# LEDs.net
KiCad netlist of a schematic drawn in Altium Designer
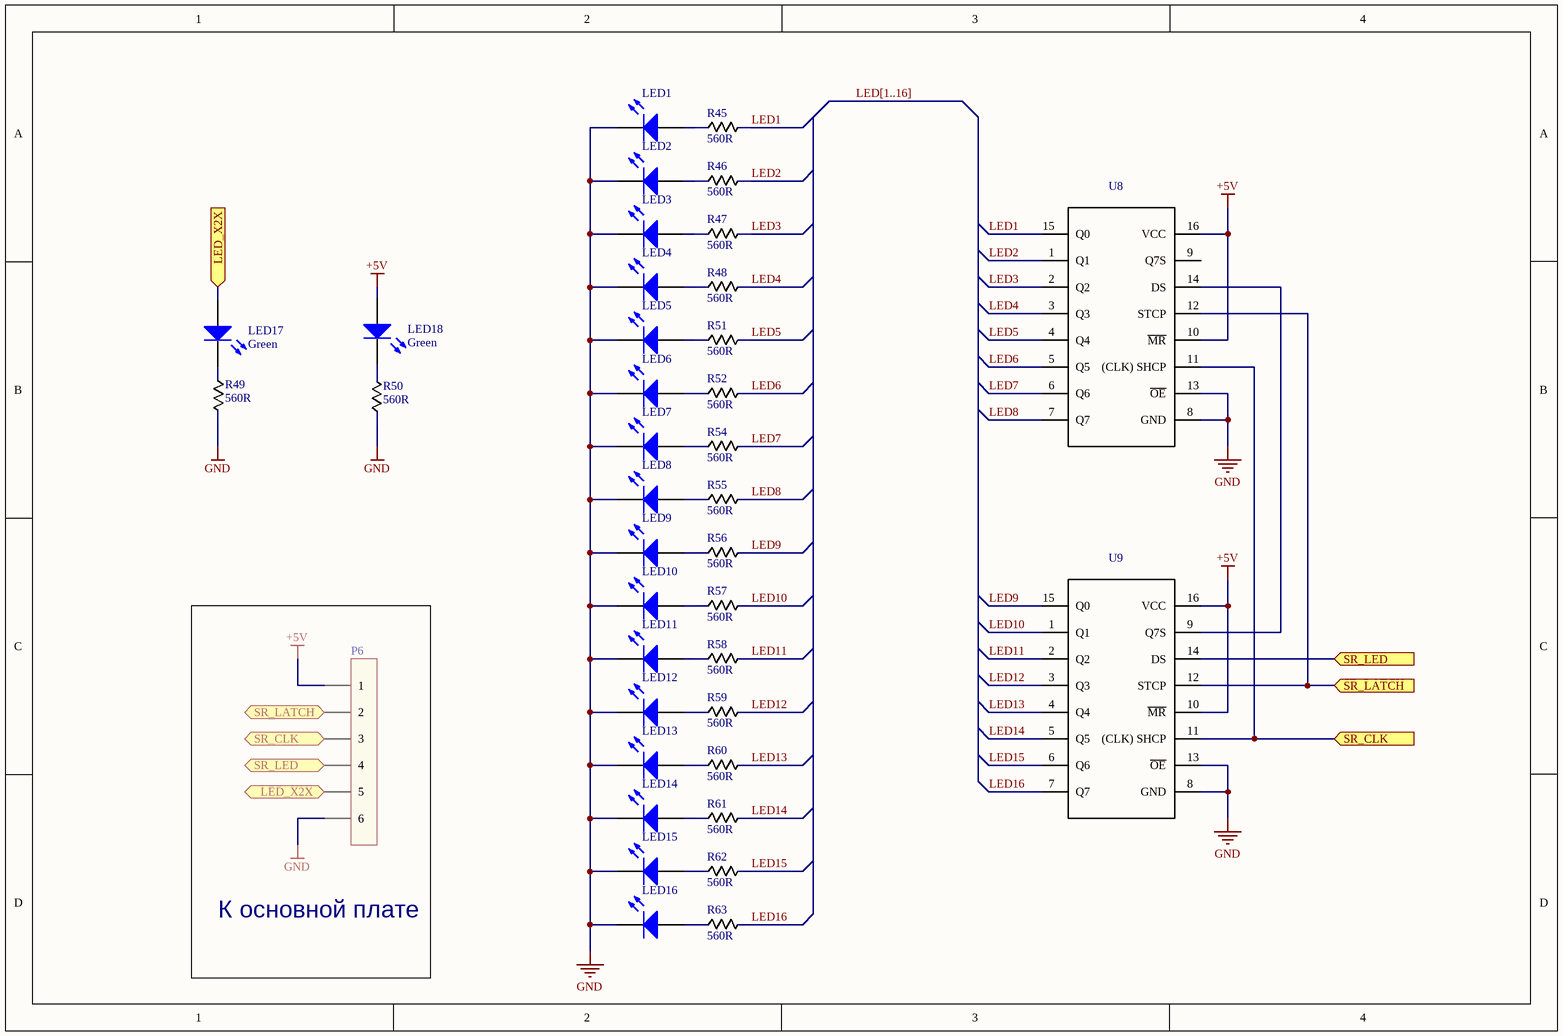
[diagram p0: LEDs.SchDoc]

(export (version "E")
  (design (tool "Eeschema 10.0.6"))
  (components
    (comp (ref "LED1")
      (value "Green")
      (footprint "LED SMD 0603")
      (fields (field (name "PART NUMBER") "KP-1608SGC"))
      (libsource (lib "kontr") (part "0603 LED"))
    )
    (comp (ref "LED2")
      (value "Green")
      (footprint "LED SMD 0603")
      (fields (field (name "PART NUMBER") "KP-1608SGC"))
      (libsource (lib "kontr") (part "0603 LED"))
    )
    (comp (ref "LED3")
      (value "Green")
      (footprint "LED SMD 0603")
      (fields (field (name "PART NUMBER") "KP-1608SGC"))
      (libsource (lib "kontr") (part "0603 LED"))
    )
    (comp (ref "LED4")
      (value "Green")
      (footprint "LED SMD 0603")
      (fields (field (name "PART NUMBER") "KP-1608SGC"))
      (libsource (lib "kontr") (part "0603 LED"))
    )
    (comp (ref "LED5")
      (value "Green")
      (footprint "LED SMD 0603")
      (fields (field (name "PART NUMBER") "KP-1608SGC"))
      (libsource (lib "kontr") (part "0603 LED"))
    )
    (comp (ref "LED6")
      (value "Green")
      (footprint "LED SMD 0603")
      (fields (field (name "PART NUMBER") "KP-1608SGC"))
      (libsource (lib "kontr") (part "0603 LED"))
    )
    (comp (ref "LED7")
      (value "Green")
      (footprint "LED SMD 0603")
      (fields (field (name "PART NUMBER") "KP-1608SGC"))
      (libsource (lib "kontr") (part "0603 LED"))
    )
    (comp (ref "LED8")
      (value "Green")
      (footprint "LED SMD 0603")
      (fields (field (name "PART NUMBER") "KP-1608SGC"))
      (libsource (lib "kontr") (part "0603 LED"))
    )
    (comp (ref "LED9")
      (value "Green")
      (footprint "LED SMD 0603")
      (fields (field (name "PART NUMBER") "KP-1608SGC"))
      (libsource (lib "kontr") (part "0603 LED"))
    )
    (comp (ref "LED10")
      (value "Green")
      (footprint "LED SMD 0603")
      (fields (field (name "PART NUMBER") "KP-1608SGC"))
      (libsource (lib "kontr") (part "0603 LED"))
    )
    (comp (ref "LED11")
      (value "Green")
      (footprint "LED SMD 0603")
      (fields (field (name "PART NUMBER") "KP-1608SGC"))
      (libsource (lib "kontr") (part "0603 LED"))
    )
    (comp (ref "LED12")
      (value "Green")
      (footprint "LED SMD 0603")
      (fields (field (name "PART NUMBER") "KP-1608SGC"))
      (libsource (lib "kontr") (part "0603 LED"))
    )
    (comp (ref "LED13")
      (value "Green")
      (footprint "LED SMD 0603")
      (fields (field (name "PART NUMBER") "KP-1608SGC"))
      (libsource (lib "kontr") (part "0603 LED"))
    )
    (comp (ref "LED14")
      (value "Green")
      (footprint "LED SMD 0603")
      (fields (field (name "PART NUMBER") "KP-1608SGC"))
      (libsource (lib "kontr") (part "0603 LED"))
    )
    (comp (ref "LED15")
      (value "Green")
      (footprint "LED SMD 0603")
      (fields (field (name "PART NUMBER") "KP-1608SGC"))
      (libsource (lib "kontr") (part "0603 LED"))
    )
    (comp (ref "LED16")
      (value "Green")
      (footprint "LED SMD 0603")
      (fields (field (name "PART NUMBER") "KP-1608SGC"))
      (libsource (lib "kontr") (part "0603 LED"))
    )
    (comp (ref "LED17")
      (value "Green")
      (footprint "LED SMD 0603")
      (fields (field (name "PART NUMBER") "KP-1608SGC"))
      (libsource (lib "kontr") (part "0603 LED"))
    )
    (comp (ref "LED18")
      (value "Green")
      (footprint "LED SMD 0603")
      (fields (field (name "PART NUMBER") "KP-1608SGC"))
      (libsource (lib "kontr") (part "0603 LED"))
    )
    (comp (ref "P6")
      (value "~")
      (footprint "МЦТР.00010592.00.002:PLS-6 2.54")
      (fields (field (name "PART NUMBER") "PLS-6"))
      (libsource (lib "levin") (part "PLS-6"))
    )
    (comp (ref "R45")
      (value "560R")
      (footprint "0603_RES")
      (fields (field (name "PART NUMBER") "RC0603JR-07560RL"))
      (libsource (lib "kontr") (part "0603 RES"))
    )
    (comp (ref "R46")
      (value "560R")
      (footprint "0603_RES")
      (fields (field (name "PART NUMBER") "RC0603JR-07560RL"))
      (libsource (lib "kontr") (part "0603 RES"))
    )
    (comp (ref "R47")
      (value "560R")
      (footprint "0603_RES")
      (fields (field (name "PART NUMBER") "RC0603JR-07560RL"))
      (libsource (lib "kontr") (part "0603 RES"))
    )
    (comp (ref "R48")
      (value "560R")
      (footprint "0603_RES")
      (fields (field (name "PART NUMBER") "RC0603JR-07560RL"))
      (libsource (lib "kontr") (part "0603 RES"))
    )
    (comp (ref "R49")
      (value "560R")
      (footprint "0603_RES")
      (fields (field (name "PART NUMBER") "RC0603JR-07560RL"))
      (libsource (lib "kontr") (part "0603 RES"))
    )
    (comp (ref "R50")
      (value "560R")
      (footprint "0603_RES")
      (fields (field (name "PART NUMBER") "RC0603JR-07560RL"))
      (libsource (lib "kontr") (part "0603 RES"))
    )
    (comp (ref "R51")
      (value "560R")
      (footprint "0603_RES")
      (fields (field (name "PART NUMBER") "RC0603JR-07560RL"))
      (libsource (lib "kontr") (part "0603 RES"))
    )
    (comp (ref "R52")
      (value "560R")
      (footprint "0603_RES")
      (fields (field (name "PART NUMBER") "RC0603JR-07560RL"))
      (libsource (lib "kontr") (part "0603 RES"))
    )
    (comp (ref "R54")
      (value "560R")
      (footprint "0603_RES")
      (fields (field (name "PART NUMBER") "RC0603JR-07560RL"))
      (libsource (lib "kontr") (part "0603 RES"))
    )
    (comp (ref "R55")
      (value "560R")
      (footprint "0603_RES")
      (fields (field (name "PART NUMBER") "RC0603JR-07560RL"))
      (libsource (lib "kontr") (part "0603 RES"))
    )
    (comp (ref "R56")
      (value "560R")
      (footprint "0603_RES")
      (fields (field (name "PART NUMBER") "RC0603JR-07560RL"))
      (libsource (lib "kontr") (part "0603 RES"))
    )
    (comp (ref "R57")
      (value "560R")
      (footprint "0603_RES")
      (fields (field (name "PART NUMBER") "RC0603JR-07560RL"))
      (libsource (lib "kontr") (part "0603 RES"))
    )
    (comp (ref "R58")
      (value "560R")
      (footprint "0603_RES")
      (fields (field (name "PART NUMBER") "RC0603JR-07560RL"))
      (libsource (lib "kontr") (part "0603 RES"))
    )
    (comp (ref "R59")
      (value "560R")
      (footprint "0603_RES")
      (fields (field (name "PART NUMBER") "RC0603JR-07560RL"))
      (libsource (lib "kontr") (part "0603 RES"))
    )
    (comp (ref "R60")
      (value "560R")
      (footprint "0603_RES")
      (fields (field (name "PART NUMBER") "RC0603JR-07560RL"))
      (libsource (lib "kontr") (part "0603 RES"))
    )
    (comp (ref "R61")
      (value "560R")
      (footprint "0603_RES")
      (fields (field (name "PART NUMBER") "RC0603JR-07560RL"))
      (libsource (lib "kontr") (part "0603 RES"))
    )
    (comp (ref "R62")
      (value "560R")
      (footprint "0603_RES")
      (fields (field (name "PART NUMBER") "RC0603JR-07560RL"))
      (libsource (lib "kontr") (part "0603 RES"))
    )
    (comp (ref "R63")
      (value "560R")
      (footprint "0603_RES")
      (fields (field (name "PART NUMBER") "RC0603JR-07560RL"))
      (libsource (lib "kontr") (part "0603 RES"))
    )
    (comp (ref "U8")
      (value "~")
      (footprint "SOIC 16")
      (fields (field (name "PART NUMBER") "74HC595D.118"))
      (libsource (lib "74hc595") (part "74HC595"))
    )
    (comp (ref "U9")
      (value "~")
      (footprint "SOIC 16")
      (fields (field (name "PART NUMBER") "74HC595D.118"))
      (libsource (lib "74hc595") (part "74HC595"))
    )
  )
  (nets
    (net (code "1") (name "+5V") (class "Default")
      (node (ref "LED18") (pin "1") (pinfunction "A_1") (pintype "passive"))
      (node (ref "P6") (pin "1") (pinfunction "1_1") (pintype "passive"))
      (node (ref "U8") (pin "10") (pinfunction "~{MR}_10") (pintype "passive"))
      (node (ref "U8") (pin "16") (pinfunction "VCC_16") (pintype "passive"))
      (node (ref "U9") (pin "10") (pinfunction "~{MR}_10") (pintype "passive"))
      (node (ref "U9") (pin "16") (pinfunction "VCC_16") (pintype "passive"))
    )
    (net (code "2") (name "/LED1") (class "Default")
      (node (ref "R45") (pin "2") (pintype "passive"))
      (node (ref "U8") (pin "15") (pinfunction "Q0_15") (pintype "passive"))
    )
    (net (code "3") (name "/LED2") (class "Default")
      (node (ref "R46") (pin "2") (pintype "passive"))
      (node (ref "U8") (pin "1") (pinfunction "Q1_1") (pintype "passive"))
    )
    (net (code "4") (name "/LED3") (class "Default")
      (node (ref "R47") (pin "2") (pintype "passive"))
      (node (ref "U8") (pin "2") (pinfunction "Q2_2") (pintype "passive"))
    )
    (net (code "5") (name "/LED4") (class "Default")
      (node (ref "R48") (pin "2") (pintype "passive"))
      (node (ref "U8") (pin "3") (pinfunction "Q3_3") (pintype "passive"))
    )
    (net (code "6") (name "/LED5") (class "Default")
      (node (ref "R51") (pin "2") (pintype "passive"))
      (node (ref "U8") (pin "4") (pinfunction "Q4_4") (pintype "passive"))
    )
    (net (code "7") (name "/LED6") (class "Default")
      (node (ref "R52") (pin "2") (pintype "passive"))
      (node (ref "U8") (pin "5") (pinfunction "Q5_5") (pintype "passive"))
    )
    (net (code "8") (name "/LED7") (class "Default")
      (node (ref "R54") (pin "2") (pintype "passive"))
      (node (ref "U8") (pin "6") (pinfunction "Q6_6") (pintype "passive"))
    )
    (net (code "9") (name "/LED8") (class "Default")
      (node (ref "R55") (pin "2") (pintype "passive"))
      (node (ref "U8") (pin "7") (pinfunction "Q7_7") (pintype "passive"))
    )
    (net (code "10") (name "/LED9") (class "Default")
      (node (ref "R56") (pin "2") (pintype "passive"))
      (node (ref "U9") (pin "15") (pinfunction "Q0_15") (pintype "passive"))
    )
    (net (code "11") (name "/LED10") (class "Default")
      (node (ref "R57") (pin "2") (pintype "passive"))
      (node (ref "U9") (pin "1") (pinfunction "Q1_1") (pintype "passive"))
    )
    (net (code "12") (name "/LED11") (class "Default")
      (node (ref "R58") (pin "2") (pintype "passive"))
      (node (ref "U9") (pin "2") (pinfunction "Q2_2") (pintype "passive"))
    )
    (net (code "13") (name "/LED12") (class "Default")
      (node (ref "R59") (pin "2") (pintype "passive"))
      (node (ref "U9") (pin "3") (pinfunction "Q3_3") (pintype "passive"))
    )
    (net (code "14") (name "/LED13") (class "Default")
      (node (ref "R60") (pin "2") (pintype "passive"))
      (node (ref "U9") (pin "4") (pinfunction "Q4_4") (pintype "passive"))
    )
    (net (code "15") (name "/LED14") (class "Default")
      (node (ref "R61") (pin "2") (pintype "passive"))
      (node (ref "U9") (pin "5") (pinfunction "Q5_5") (pintype "passive"))
    )
    (net (code "16") (name "/LED15") (class "Default")
      (node (ref "R62") (pin "2") (pintype "passive"))
      (node (ref "U9") (pin "6") (pinfunction "Q6_6") (pintype "passive"))
    )
    (net (code "17") (name "/LED16") (class "Default")
      (node (ref "R63") (pin "2") (pintype "passive"))
      (node (ref "U9") (pin "7") (pinfunction "Q7_7") (pintype "passive"))
    )
    (net (code "19") (name "/LED_X2X") (class "Default")
      (node (ref "LED17") (pin "1") (pinfunction "A_1") (pintype "passive"))
      (node (ref "P6") (pin "5") (pinfunction "5_5") (pintype "passive"))
    )
    (net (code "20") (name "/SR_CLK") (class "Default")
      (node (ref "P6") (pin "3") (pinfunction "3_3") (pintype "passive"))
      (node (ref "U8") (pin "11") (pinfunction "(CLK)_SHCP_11") (pintype "passive"))
      (node (ref "U9") (pin "11") (pinfunction "(CLK)_SHCP_11") (pintype "passive"))
    )
    (net (code "21") (name "/SR_LATCH") (class "Default")
      (node (ref "P6") (pin "2") (pinfunction "2_2") (pintype "passive"))
      (node (ref "U8") (pin "12") (pinfunction "STCP_12") (pintype "passive"))
      (node (ref "U9") (pin "12") (pinfunction "STCP_12") (pintype "passive"))
    )
    (net (code "22") (name "/SR_LED") (class "Default")
      (node (ref "P6") (pin "4") (pinfunction "4_4") (pintype "passive"))
      (node (ref "U9") (pin "14") (pinfunction "DS_14") (pintype "passive"))
    )
    (net (code "23") (name "GND") (class "Default")
      (node (ref "LED1") (pin "2") (pinfunction "K_2") (pintype "passive"))
      (node (ref "LED10") (pin "2") (pinfunction "K_2") (pintype "passive"))
      (node (ref "LED11") (pin "2") (pinfunction "K_2") (pintype "passive"))
      (node (ref "LED12") (pin "2") (pinfunction "K_2") (pintype "passive"))
      (node (ref "LED13") (pin "2") (pinfunction "K_2") (pintype "passive"))
      (node (ref "LED14") (pin "2") (pinfunction "K_2") (pintype "passive"))
      (node (ref "LED15") (pin "2") (pinfunction "K_2") (pintype "passive"))
      (node (ref "LED16") (pin "2") (pinfunction "K_2") (pintype "passive"))
      (node (ref "LED2") (pin "2") (pinfunction "K_2") (pintype "passive"))
      (node (ref "LED3") (pin "2") (pinfunction "K_2") (pintype "passive"))
      (node (ref "LED4") (pin "2") (pinfunction "K_2") (pintype "passive"))
      (node (ref "LED5") (pin "2") (pinfunction "K_2") (pintype "passive"))
      (node (ref "LED6") (pin "2") (pinfunction "K_2") (pintype "passive"))
      (node (ref "LED7") (pin "2") (pinfunction "K_2") (pintype "passive"))
      (node (ref "LED8") (pin "2") (pinfunction "K_2") (pintype "passive"))
      (node (ref "LED9") (pin "2") (pinfunction "K_2") (pintype "passive"))
      (node (ref "P6") (pin "6") (pinfunction "6_6") (pintype "passive"))
      (node (ref "R49") (pin "2") (pintype "passive"))
      (node (ref "R50") (pin "1") (pintype "passive"))
      (node (ref "U8") (pin "13") (pinfunction "~{OE}_13") (pintype "passive"))
      (node (ref "U8") (pin "8") (pinfunction "GND_8") (pintype "passive"))
      (node (ref "U9") (pin "13") (pinfunction "~{OE}_13") (pintype "passive"))
      (node (ref "U9") (pin "8") (pinfunction "GND_8") (pintype "passive"))
    )
    (net (code "24") (name "Net-(LED1-A)") (class "Default")
      (node (ref "LED1") (pin "1") (pinfunction "A_1") (pintype "passive"))
      (node (ref "R45") (pin "1") (pintype "passive"))
    )
    (net (code "25") (name "Net-(LED2-A)") (class "Default")
      (node (ref "LED2") (pin "1") (pinfunction "A_1") (pintype "passive"))
      (node (ref "R46") (pin "1") (pintype "passive"))
    )
    (net (code "26") (name "Net-(LED3-A)") (class "Default")
      (node (ref "LED3") (pin "1") (pinfunction "A_1") (pintype "passive"))
      (node (ref "R47") (pin "1") (pintype "passive"))
    )
    (net (code "27") (name "Net-(LED4-A)") (class "Default")
      (node (ref "LED4") (pin "1") (pinfunction "A_1") (pintype "passive"))
      (node (ref "R48") (pin "1") (pintype "passive"))
    )
    (net (code "28") (name "Net-(LED5-A)") (class "Default")
      (node (ref "LED5") (pin "1") (pinfunction "A_1") (pintype "passive"))
      (node (ref "R51") (pin "1") (pintype "passive"))
    )
    (net (code "29") (name "Net-(LED6-A)") (class "Default")
      (node (ref "LED6") (pin "1") (pinfunction "A_1") (pintype "passive"))
      (node (ref "R52") (pin "1") (pintype "passive"))
    )
    (net (code "30") (name "Net-(LED7-A)") (class "Default")
      (node (ref "LED7") (pin "1") (pinfunction "A_1") (pintype "passive"))
      (node (ref "R54") (pin "1") (pintype "passive"))
    )
    (net (code "31") (name "Net-(LED8-A)") (class "Default")
      (node (ref "LED8") (pin "1") (pinfunction "A_1") (pintype "passive"))
      (node (ref "R55") (pin "1") (pintype "passive"))
    )
    (net (code "32") (name "Net-(LED9-A)") (class "Default")
      (node (ref "LED9") (pin "1") (pinfunction "A_1") (pintype "passive"))
      (node (ref "R56") (pin "1") (pintype "passive"))
    )
    (net (code "33") (name "Net-(LED10-A)") (class "Default")
      (node (ref "LED10") (pin "1") (pinfunction "A_1") (pintype "passive"))
      (node (ref "R57") (pin "1") (pintype "passive"))
    )
    (net (code "34") (name "Net-(LED11-A)") (class "Default")
      (node (ref "LED11") (pin "1") (pinfunction "A_1") (pintype "passive"))
      (node (ref "R58") (pin "1") (pintype "passive"))
    )
    (net (code "35") (name "Net-(LED12-A)") (class "Default")
      (node (ref "LED12") (pin "1") (pinfunction "A_1") (pintype "passive"))
      (node (ref "R59") (pin "1") (pintype "passive"))
    )
    (net (code "36") (name "Net-(LED13-A)") (class "Default")
      (node (ref "LED13") (pin "1") (pinfunction "A_1") (pintype "passive"))
      (node (ref "R60") (pin "1") (pintype "passive"))
    )
    (net (code "37") (name "Net-(LED14-A)") (class "Default")
      (node (ref "LED14") (pin "1") (pinfunction "A_1") (pintype "passive"))
      (node (ref "R61") (pin "1") (pintype "passive"))
    )
    (net (code "38") (name "Net-(LED15-A)") (class "Default")
      (node (ref "LED15") (pin "1") (pinfunction "A_1") (pintype "passive"))
      (node (ref "R62") (pin "1") (pintype "passive"))
    )
    (net (code "39") (name "Net-(LED16-A)") (class "Default")
      (node (ref "LED16") (pin "1") (pinfunction "A_1") (pintype "passive"))
      (node (ref "R63") (pin "1") (pintype "passive"))
    )
    (net (code "40") (name "Net-(LED17-K)") (class "Default")
      (node (ref "LED17") (pin "2") (pinfunction "K_2") (pintype "passive"))
      (node (ref "R49") (pin "1") (pintype "passive"))
    )
    (net (code "41") (name "Net-(LED18-K)") (class "Default")
      (node (ref "LED18") (pin "2") (pinfunction "K_2") (pintype "passive"))
      (node (ref "R50") (pin "2") (pintype "passive"))
    )
    (net (code "42") (name "Net-(U8-DS)") (class "Default")
      (node (ref "U8") (pin "14") (pinfunction "DS_14") (pintype "passive"))
      (node (ref "U9") (pin "9") (pinfunction "Q7S_9") (pintype "passive"))
    )
    (net (code "43") (name "unconnected-(U8-Q7S-Pad9)") (class "Default")
      (node (ref "U8") (pin "9") (pinfunction "Q7S_9") (pintype "passive"))
    )
  )
)
